# design.net
KiCad netlist of a schematic drawn in Altium Designer
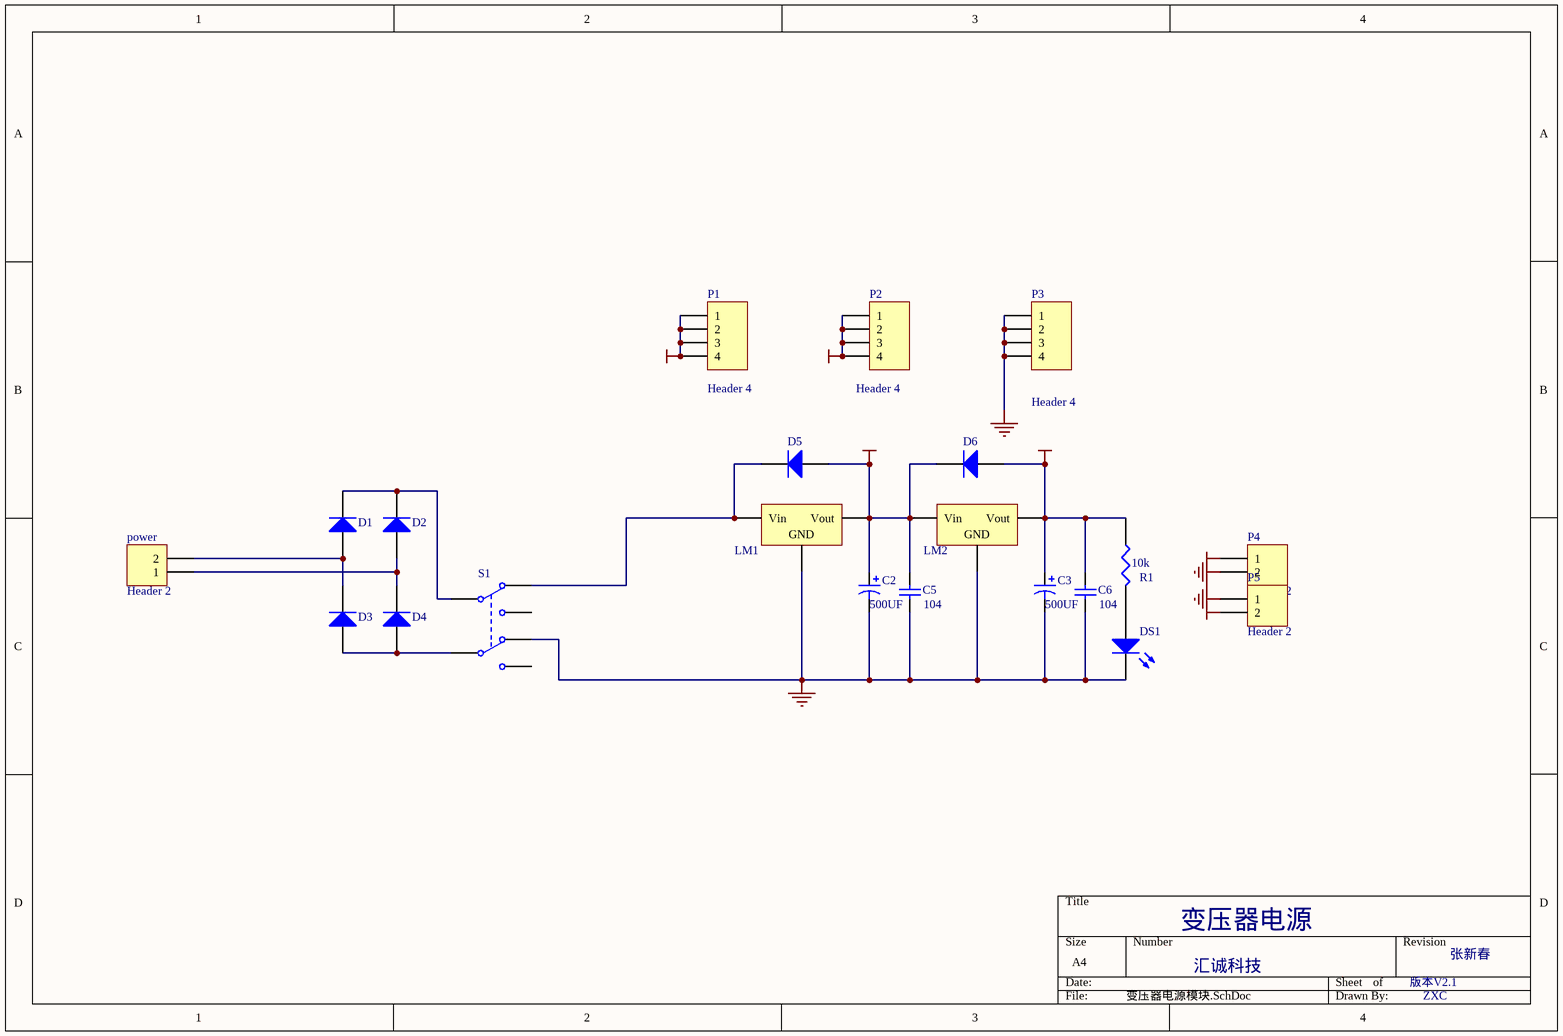
[diagram p0: 变压器电源模块.SchDoc]

(export (version "E")
  (design (tool "Eeschema 10.0.6"))
  (components
    (comp (ref "C2")
      (value "500UF")
      (footprint "C 220/50")
      (description "Polarized Capacitor (Radial)")
      (fields (field (name "PUBLISHER") "Altium Limited"))
      (libsource (lib "Miscellaneous Devices") (part "Cap Pol1"))
    )
    (comp (ref "C3")
      (value "500UF")
      (footprint "C 220/50")
      (description "Polarized Capacitor (Radial)")
      (fields (field (name "PUBLISHER") "Altium Limited"))
      (libsource (lib "Miscellaneous Devices") (part "Cap Pol1"))
    )
    (comp (ref "C5")
      (value "104")
      (footprint "HDR1X2")
      (description "Capacitor")
      (fields (field (name "PUBLISHER") "Altium Limited"))
      (libsource (lib "Miscellaneous Devices") (part "Cap"))
    )
    (comp (ref "C6")
      (value "104")
      (footprint "HDR1X2")
      (description "Capacitor")
      (fields (field (name "PUBLISHER") "Altium Limited"))
      (libsource (lib "Miscellaneous Devices") (part "Cap"))
    )
    (comp (ref "D1")
      (value "~")
      (footprint "DIO7.8-4.6x2")
      (description "1 Amp General Purpose Rectifier")
      (fields (field (name "PUBLISHER") "Altium Limited"))
      (libsource (lib "Miscellaneous Devices") (part "Diode 1N4007"))
    )
    (comp (ref "D2")
      (value "~")
      (footprint "DIO7.8-4.6x2")
      (description "1 Amp General Purpose Rectifier")
      (fields (field (name "PUBLISHER") "Altium Limited"))
      (libsource (lib "Miscellaneous Devices") (part "Diode 1N4007"))
    )
    (comp (ref "D3")
      (value "~")
      (footprint "DIO7.8-4.6x2")
      (description "1 Amp General Purpose Rectifier")
      (fields (field (name "PUBLISHER") "Altium Limited"))
      (libsource (lib "Miscellaneous Devices") (part "Diode 1N4007"))
    )
    (comp (ref "D4")
      (value "~")
      (footprint "DIO7.8-4.6x2")
      (description "1 Amp General Purpose Rectifier")
      (fields (field (name "PUBLISHER") "Altium Limited"))
      (libsource (lib "Miscellaneous Devices") (part "Diode 1N4007"))
    )
    (comp (ref "D5")
      (value "~")
      (footprint "DIO10.46-5.3x2.8")
      (description "1 Amp General Purpose Rectifier")
      (fields (field (name "PUBLISHER") "Altium Limited"))
      (libsource (lib "Miscellaneous Devices") (part "Diode 1N4007"))
    )
    (comp (ref "D6")
      (value "~")
      (footprint "DIO10.46-5.3x2.8")
      (description "1 Amp General Purpose Rectifier")
      (fields (field (name "PUBLISHER") "Altium Limited"))
      (libsource (lib "Miscellaneous Devices") (part "Diode 1N4007"))
    )
    (comp (ref "DS1")
      (value "~")
      (footprint "HDR1X2")
      (description "Typical INFRARED GaAs LED")
      (fields (field (name "PUBLISHER") "Altium Limited"))
      (libsource (lib "Miscellaneous Devices") (part "LED0"))
    )
    (comp (ref "LM1")
      (value "~")
      (footprint "wyk")
      (description "Voltage Regulator")
      (fields (field (name "PUBLISHER") "Altium Limited"))
      (libsource (lib "Miscellaneous Devices") (part "Volt Reg"))
    )
    (comp (ref "LM2")
      (value "~")
      (footprint "wyk")
      (description "Voltage Regulator")
      (fields (field (name "PUBLISHER") "Altium Limited"))
      (libsource (lib "Miscellaneous Devices") (part "Volt Reg"))
    )
    (comp (ref "P1")
      (value "Header 4")
      (footprint "HDR1X4")
      (description "Header, 4-Pin")
      (fields (field (name "PUBLISHER") "Altium Limited"))
      (libsource (lib "Miscellaneous Connectors") (part "Header 4"))
    )
    (comp (ref "P2")
      (value "Header 4")
      (footprint "HDR1X4")
      (description "Header, 4-Pin")
      (fields (field (name "PUBLISHER") "Altium Limited"))
      (libsource (lib "Miscellaneous Connectors") (part "Header 4"))
    )
    (comp (ref "P3")
      (value "Header 4")
      (footprint "HDR1X4")
      (description "Header, 4-Pin")
      (fields (field (name "PUBLISHER") "Altium Limited"))
      (libsource (lib "Miscellaneous Connectors") (part "Header 4"))
    )
    (comp (ref "P4")
      (value "Header 2")
      (footprint "JK128")
      (description "Header, 2-Pin")
      (fields (field (name "PUBLISHER") "Altium Limited"))
      (libsource (lib "Miscellaneous Connectors") (part "Header 2"))
    )
    (comp (ref "P5")
      (value "Header 2")
      (footprint "JK128")
      (description "Header, 2-Pin")
      (fields (field (name "PUBLISHER") "Altium Limited"))
      (libsource (lib "Miscellaneous Connectors") (part "Header 2"))
    )
    (comp (ref "power")
      (value "Header 2")
      (footprint "JK128")
      (description "Header, 2-Pin")
      (fields (field (name "PUBLISHER") "Altium Limited"))
      (libsource (lib "") (part "Header 2_1"))
    )
    (comp (ref "R1") (value "10k") (footprint "HDR1X2") (libsource (lib "*") (part "RES1")))
    (comp (ref "S1")
      (value "~")
      (footprint "DPDT-6")
      (description "Switch")
      (fields (field (name "PUBLISHER") "Altium Limited"))
      (libsource (lib "Miscellaneous Devices") (part "SW DPDT"))
    )
  )
  (nets
    (net (code "1") (name "A05") (class "Default")
      (node (ref "C3") (pin "1") (pinfunction "1_1") (pintype "passive"))
      (node (ref "C6") (pin "2") (pinfunction "2_2") (pintype "passive"))
      (node (ref "D6") (pin "1") (pinfunction "A_1") (pintype "passive"))
      (node (ref "LM2") (pin "3") (pinfunction "Vout_3") (pintype "passive"))
      (node (ref "P2") (pin "1") (pinfunction "1_1") (pintype "passive"))
      (node (ref "P2") (pin "2") (pinfunction "2_2") (pintype "passive"))
      (node (ref "P2") (pin "3") (pinfunction "3_3") (pintype "passive"))
      (node (ref "P2") (pin "4") (pinfunction "4_4") (pintype "passive"))
      (node (ref "P5") (pin "2") (pinfunction "2_2") (pintype "passive"))
      (node (ref "R1") (pin "1") (pinfunction "1_1") (pintype "passive"))
    )
    (net (code "2") (name "A12") (class "Default")
      (node (ref "C2") (pin "1") (pinfunction "1_1") (pintype "passive"))
      (node (ref "C5") (pin "2") (pinfunction "2_2") (pintype "passive"))
      (node (ref "D5") (pin "1") (pinfunction "A_1") (pintype "passive"))
      (node (ref "D6") (pin "2") (pinfunction "K_2") (pintype "passive"))
      (node (ref "LM1") (pin "3") (pinfunction "Vout_3") (pintype "passive"))
      (node (ref "LM2") (pin "1") (pinfunction "Vin_1") (pintype "passive"))
      (node (ref "P1") (pin "1") (pinfunction "1_1") (pintype "passive"))
      (node (ref "P1") (pin "2") (pinfunction "2_2") (pintype "passive"))
      (node (ref "P1") (pin "3") (pinfunction "3_3") (pintype "passive"))
      (node (ref "P1") (pin "4") (pinfunction "4_4") (pintype "passive"))
      (node (ref "P4") (pin "1") (pinfunction "1_1") (pintype "passive"))
    )
    (net (code "3") (name "AGND") (class "Default")
      (node (ref "C2") (pin "2") (pinfunction "2_2") (pintype "passive"))
      (node (ref "C3") (pin "2") (pinfunction "2_2") (pintype "passive"))
      (node (ref "C5") (pin "1") (pinfunction "1_1") (pintype "passive"))
      (node (ref "C6") (pin "1") (pinfunction "1_1") (pintype "passive"))
      (node (ref "DS1") (pin "2") (pinfunction "K_2") (pintype "passive"))
      (node (ref "LM1") (pin "2") (pinfunction "GND_2") (pintype "passive"))
      (node (ref "LM2") (pin "2") (pinfunction "GND_2") (pintype "passive"))
      (node (ref "P3") (pin "1") (pinfunction "1_1") (pintype "passive"))
      (node (ref "P3") (pin "2") (pinfunction "2_2") (pintype "passive"))
      (node (ref "P3") (pin "3") (pinfunction "3_3") (pintype "passive"))
      (node (ref "P3") (pin "4") (pinfunction "4_4") (pintype "passive"))
      (node (ref "P4") (pin "2") (pinfunction "2_2") (pintype "passive"))
      (node (ref "S1") (pin "4") (pinfunction "NC2_4") (pintype "passive"))
    )
    (net (code "4") (name "BGND") (class "Default")
      (node (ref "P5") (pin "1") (pinfunction "1_1") (pintype "passive"))
    )
    (net (code "5") (name "Net-(D1-A)") (class "Default")
      (node (ref "D1") (pin "1") (pinfunction "A_1") (pintype "passive"))
      (node (ref "D3") (pin "2") (pinfunction "K_2") (pintype "passive"))
      (node (ref "power") (pin "2") (pinfunction "2_2") (pintype "passive"))
    )
    (net (code "6") (name "Net-(D1-K)") (class "Default")
      (node (ref "D1") (pin "2") (pinfunction "K_2") (pintype "passive"))
      (node (ref "D2") (pin "2") (pinfunction "K_2") (pintype "passive"))
      (node (ref "S1") (pin "1") (pinfunction "COMMON1_1") (pintype "passive"))
    )
    (net (code "7") (name "Net-(D2-A)") (class "Default")
      (node (ref "D2") (pin "1") (pinfunction "A_1") (pintype "passive"))
      (node (ref "D4") (pin "2") (pinfunction "K_2") (pintype "passive"))
      (node (ref "power") (pin "1") (pinfunction "1_1") (pintype "passive"))
    )
    (net (code "8") (name "Net-(D3-A)") (class "Default")
      (node (ref "D3") (pin "1") (pinfunction "A_1") (pintype "passive"))
      (node (ref "D4") (pin "1") (pinfunction "A_1") (pintype "passive"))
      (node (ref "S1") (pin "5") (pinfunction "COMMON2_5") (pintype "passive"))
    )
    (net (code "9") (name "Net-(D5-K)") (class "Default")
      (node (ref "D5") (pin "2") (pinfunction "K_2") (pintype "passive"))
      (node (ref "LM1") (pin "1") (pinfunction "Vin_1") (pintype "passive"))
      (node (ref "S1") (pin "2") (pinfunction "NC1_2") (pintype "passive"))
    )
    (net (code "10") (name "Net-(DS1-A)") (class "Default")
      (node (ref "DS1") (pin "1") (pinfunction "A_1") (pintype "passive"))
      (node (ref "R1") (pin "2") (pinfunction "2_2") (pintype "passive"))
    )
    (net (code "11") (name "unconnected-(S1-NO1-Pad3)") (class "Default")
      (node (ref "S1") (pin "3") (pinfunction "NO1_3") (pintype "passive"))
    )
    (net (code "12") (name "unconnected-(S1-NO2-Pad6)") (class "Default")
      (node (ref "S1") (pin "6") (pinfunction "NO2_6") (pintype "passive"))
    )
  )
)
